# smart_doorbell.net
KiCad netlist of a schematic drawn in EasyEDA
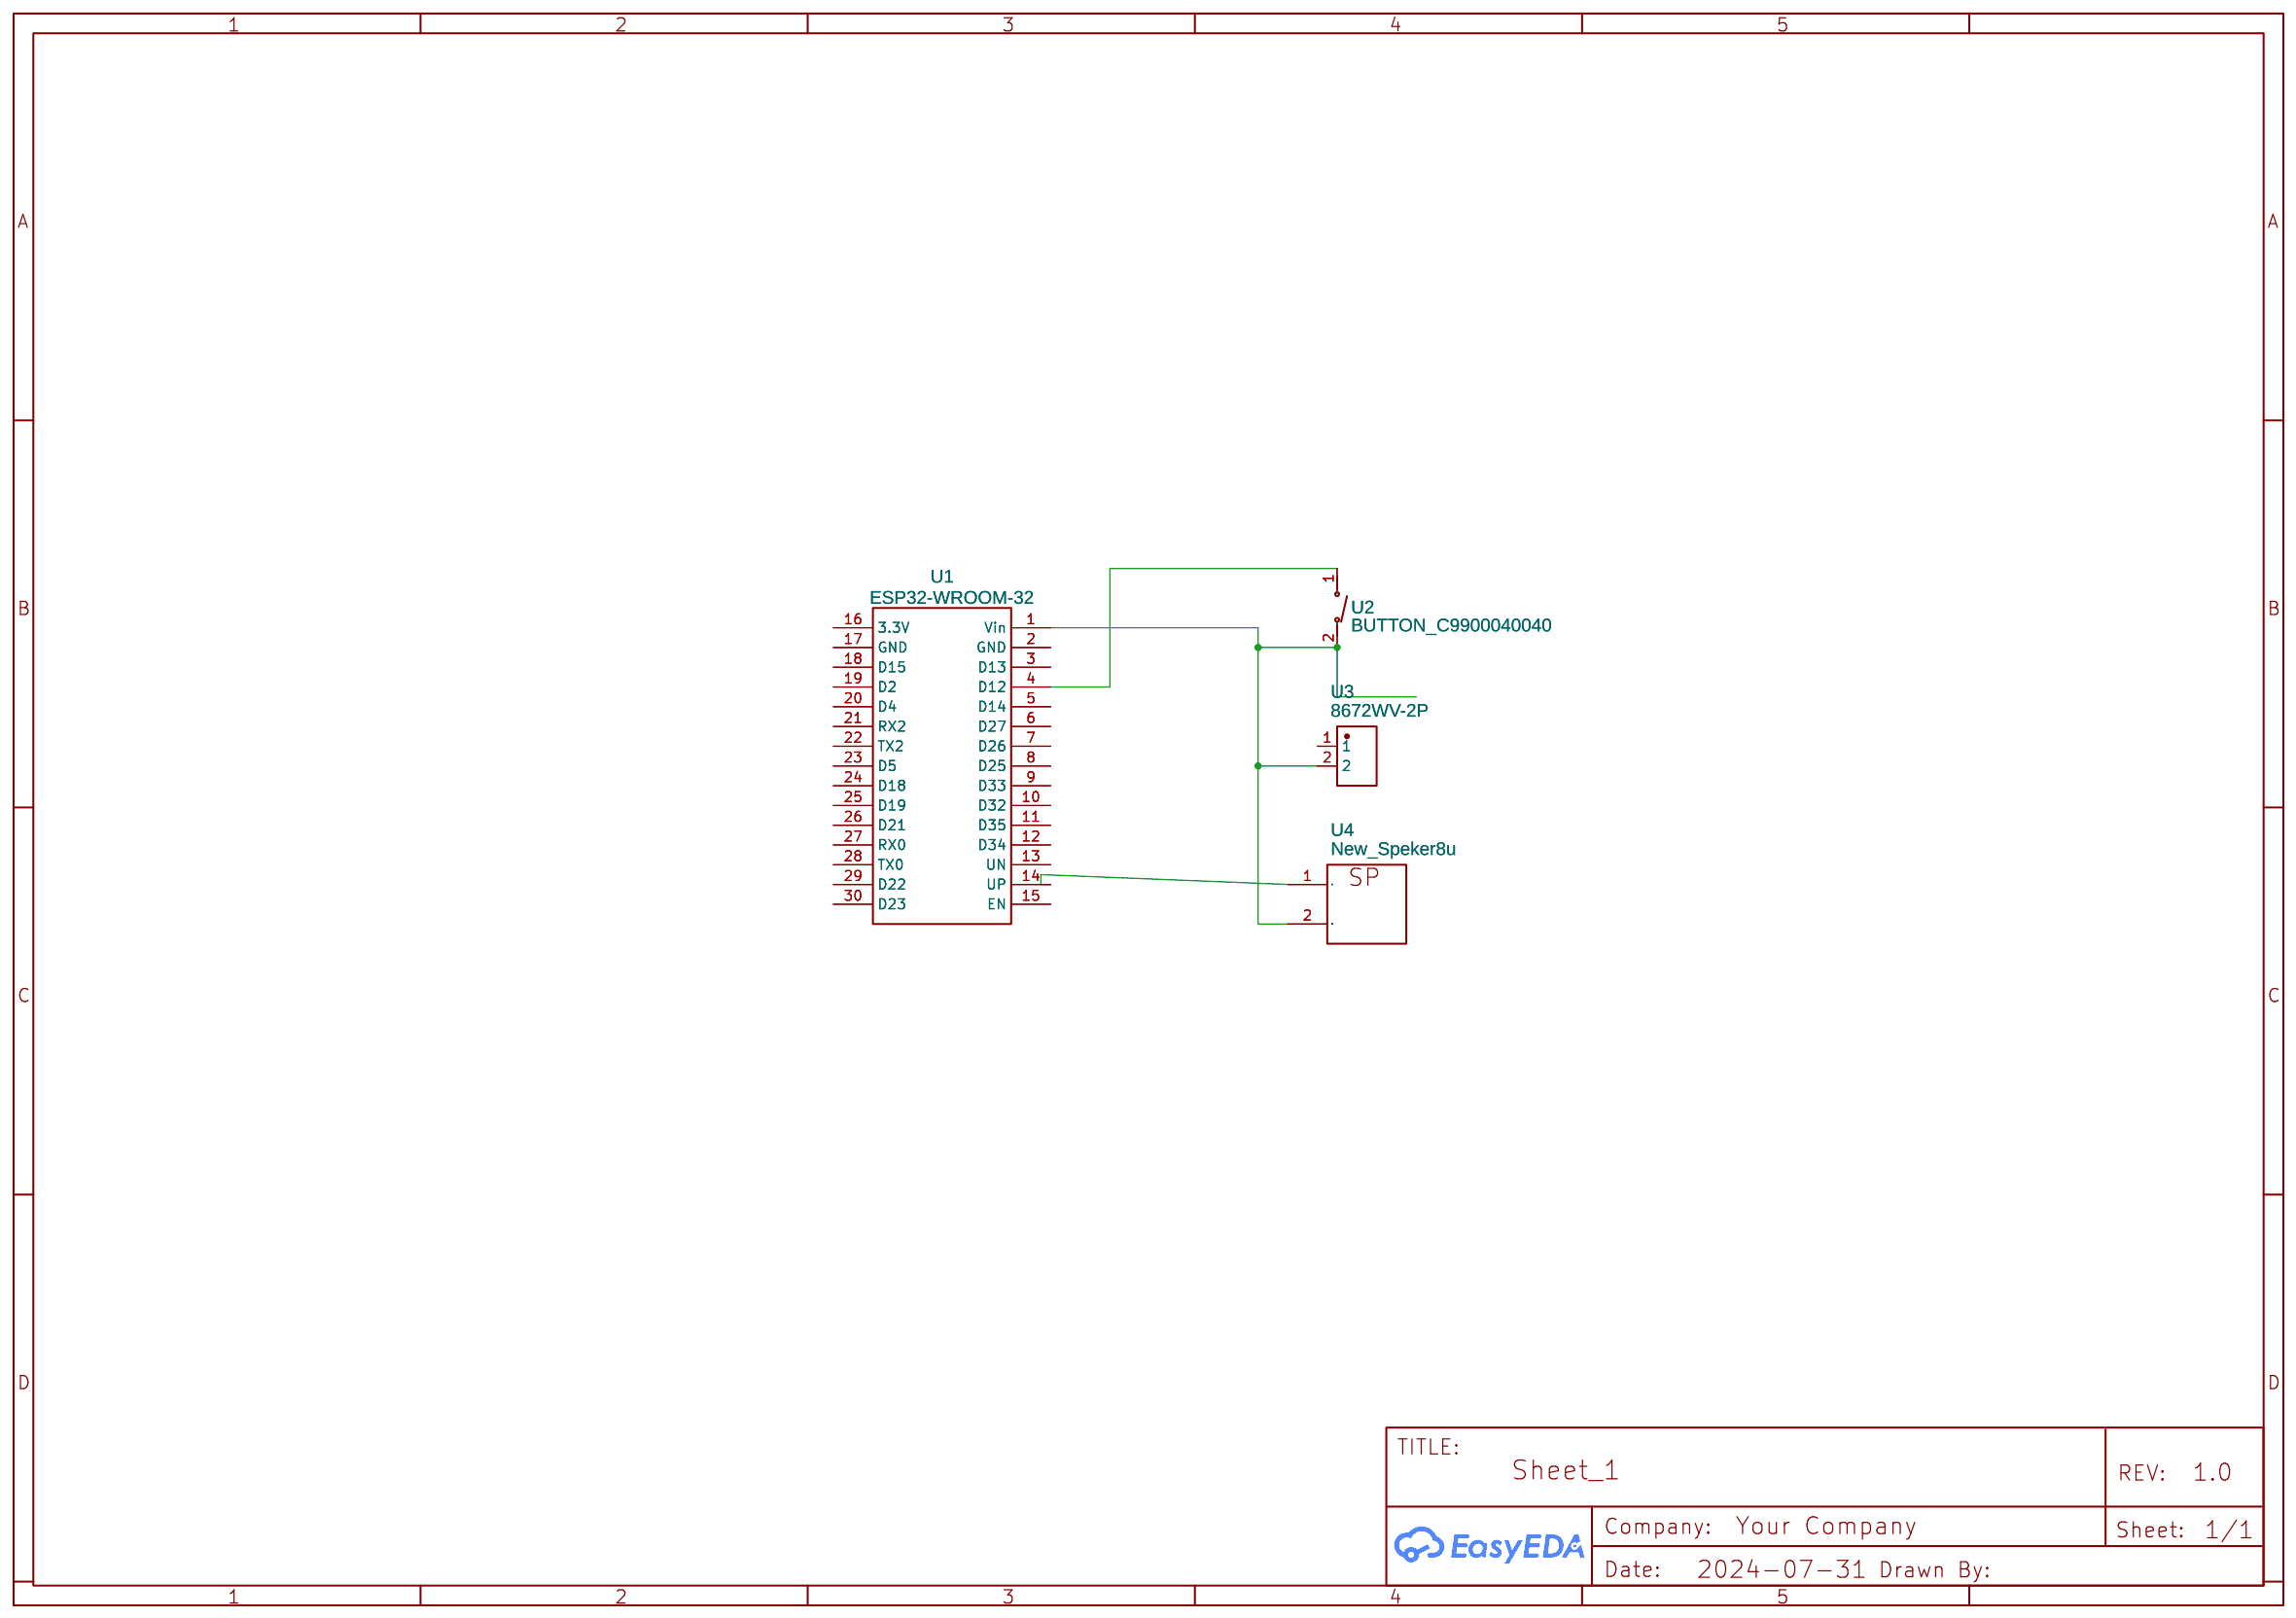
[diagram p0: schematic sheet]

(export (version "E")
  (design (tool "Eeschema 10.0.6"))
  (components
    (comp (ref "U1")
      (value "ESP32-WROOM-32")
      (fields (field (name "Manufacturer") "Espressif"))
      (libsource (lib "") (part "ESP32-WROOM-32"))
    )
    (comp (ref "U2")
      (value "BUTTON_C9900040040")
      (fields (field (name "Manufacturer Part") "BUTTON"))
      (libsource (lib "") (part "BUTTON_C9900040040"))
    )
    (comp (ref "U3")
      (value "8672WV-2P")
      (fields (field (name "Manufacturer") "HanElectricity(瀚源)"))
      (libsource (lib "") (part "8672WV-2P"))
    )
    (comp (ref "U4")
      (value "New_Speker8u")
      (fields (field (name "Manufacturer Part") "speker"))
      (libsource (lib "") (part "New_Speker8u"))
    )
  )
  (nets
    (net (code "1") (name "Net-(U1-D12)") (class "Default")
      (node (ref "U1") (pin "4") (pinfunction "D12_4") (pintype "unspecified"))
      (node (ref "U2") (pin "1") (pinfunction "A_1") (pintype "unspecified"))
    )
    (net (code "2") (name "Net-(U1-UP)") (class "Default")
      (node (ref "U1") (pin "14") (pinfunction "UP_14") (pintype "unspecified"))
      (node (ref "U4") (pin "1") (pinfunction "1_1") (pintype "unspecified"))
    )
    (net (code "3") (name "Net-(U1-Vin)") (class "Default")
      (node (ref "U1") (pin "1") (pinfunction "Vin_1") (pintype "unspecified"))
      (node (ref "U2") (pin "2") (pinfunction "B_2") (pintype "unspecified"))
      (node (ref "U3") (pin "2") (pinfunction "2_2") (pintype "unspecified"))
      (node (ref "U4") (pin "2") (pinfunction "2_2") (pintype "unspecified"))
    )
    (net (code "4") (name "unconnected-(U1-3.3V-Pad16)") (class "Default")
      (node (ref "U1") (pin "16") (pinfunction "3.3V_16") (pintype "unspecified"))
    )
    (net (code "5") (name "unconnected-(U1-D2-Pad19)") (class "Default")
      (node (ref "U1") (pin "19") (pinfunction "D2_19") (pintype "unspecified"))
    )
    (net (code "6") (name "unconnected-(U1-D4-Pad20)") (class "Default")
      (node (ref "U1") (pin "20") (pinfunction "D4_20") (pintype "unspecified"))
    )
    (net (code "7") (name "unconnected-(U1-D5-Pad23)") (class "Default")
      (node (ref "U1") (pin "23") (pinfunction "D5_23") (pintype "unspecified"))
    )
    (net (code "8") (name "unconnected-(U1-D13-Pad3)") (class "Default")
      (node (ref "U1") (pin "3") (pinfunction "D13_3") (pintype "unspecified"))
    )
    (net (code "9") (name "unconnected-(U1-D14-Pad5)") (class "Default")
      (node (ref "U1") (pin "5") (pinfunction "D14_5") (pintype "unspecified"))
    )
    (net (code "10") (name "unconnected-(U1-D15-Pad18)") (class "Default")
      (node (ref "U1") (pin "18") (pinfunction "D15_18") (pintype "unspecified"))
    )
    (net (code "11") (name "unconnected-(U1-D18-Pad24)") (class "Default")
      (node (ref "U1") (pin "24") (pinfunction "D18_24") (pintype "unspecified"))
    )
    (net (code "12") (name "unconnected-(U1-D19-Pad25)") (class "Default")
      (node (ref "U1") (pin "25") (pinfunction "D19_25") (pintype "unspecified"))
    )
    (net (code "13") (name "unconnected-(U1-D21-Pad26)") (class "Default")
      (node (ref "U1") (pin "26") (pinfunction "D21_26") (pintype "unspecified"))
    )
    (net (code "14") (name "unconnected-(U1-D22-Pad29)") (class "Default")
      (node (ref "U1") (pin "29") (pinfunction "D22_29") (pintype "unspecified"))
    )
    (net (code "15") (name "unconnected-(U1-D23-Pad30)") (class "Default")
      (node (ref "U1") (pin "30") (pinfunction "D23_30") (pintype "unspecified"))
    )
    (net (code "16") (name "unconnected-(U1-D25-Pad8)") (class "Default")
      (node (ref "U1") (pin "8") (pinfunction "D25_8") (pintype "unspecified"))
    )
    (net (code "17") (name "unconnected-(U1-D26-Pad7)") (class "Default")
      (node (ref "U1") (pin "7") (pinfunction "D26_7") (pintype "unspecified"))
    )
    (net (code "18") (name "unconnected-(U1-D27-Pad6)") (class "Default")
      (node (ref "U1") (pin "6") (pinfunction "D27_6") (pintype "unspecified"))
    )
    (net (code "19") (name "unconnected-(U1-D32-Pad10)") (class "Default")
      (node (ref "U1") (pin "10") (pinfunction "D32_10") (pintype "unspecified"))
    )
    (net (code "20") (name "unconnected-(U1-D33-Pad9)") (class "Default")
      (node (ref "U1") (pin "9") (pinfunction "D33_9") (pintype "unspecified"))
    )
    (net (code "21") (name "unconnected-(U1-D34-Pad12)") (class "Default")
      (node (ref "U1") (pin "12") (pinfunction "D34_12") (pintype "unspecified"))
    )
    (net (code "22") (name "unconnected-(U1-D35-Pad11)") (class "Default")
      (node (ref "U1") (pin "11") (pinfunction "D35_11") (pintype "unspecified"))
    )
    (net (code "23") (name "unconnected-(U1-EN-Pad15)") (class "Default")
      (node (ref "U1") (pin "15") (pinfunction "EN_15") (pintype "unspecified"))
    )
    (net (code "24") (name "unconnected-(U1-GND-Pad2)") (class "Default")
      (node (ref "U1") (pin "2") (pinfunction "GND_2") (pintype "unspecified"))
    )
    (net (code "25") (name "unconnected-(U1-GND-Pad17)") (class "Default")
      (node (ref "U1") (pin "17") (pinfunction "GND_17") (pintype "unspecified"))
    )
    (net (code "26") (name "unconnected-(U1-RX0-Pad27)") (class "Default")
      (node (ref "U1") (pin "27") (pinfunction "RX0_27") (pintype "unspecified"))
    )
    (net (code "27") (name "unconnected-(U1-RX2-Pad21)") (class "Default")
      (node (ref "U1") (pin "21") (pinfunction "RX2_21") (pintype "unspecified"))
    )
    (net (code "28") (name "unconnected-(U1-TX0-Pad28)") (class "Default")
      (node (ref "U1") (pin "28") (pinfunction "TX0_28") (pintype "unspecified"))
    )
    (net (code "29") (name "unconnected-(U1-TX2-Pad22)") (class "Default")
      (node (ref "U1") (pin "22") (pinfunction "TX2_22") (pintype "unspecified"))
    )
    (net (code "30") (name "unconnected-(U1-UN-Pad13)") (class "Default")
      (node (ref "U1") (pin "13") (pinfunction "UN_13") (pintype "unspecified"))
    )
    (net (code "31") (name "unconnected-(U3-Pad1)") (class "Default")
      (node (ref "U3") (pin "1") (pinfunction "1_1") (pintype "unspecified"))
    )
  )
)
